# final.net
KiCad netlist of a schematic drawn in EAGLE
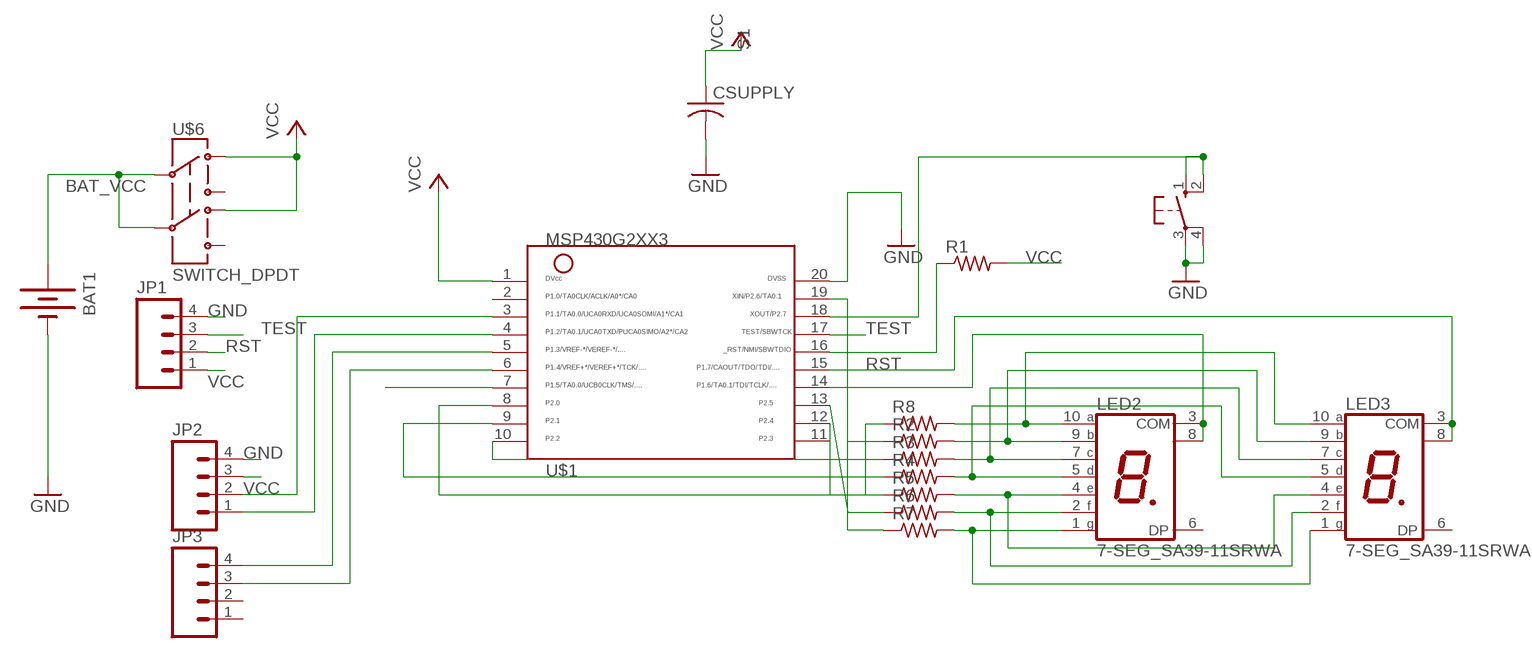
[diagram p0: schematic, sheet 1]

(export (version "E")
  (design (tool "Eeschema 10.0.6"))
  (components
    (comp (ref "BAT1")
      (value "BATTERYBU2032SM")
      (footprint "eagle-import:BU2032SM")
      (libsource (lib "eagle-import") (part "BATTERYBU2032SM"))
    )
    (comp (ref "CSUPPLY")
      (value "C-USC1206")
      (footprint "eagle-import:C1206")
      (libsource (lib "eagle-import") (part "C-USC1206"))
    )
    (comp (ref "JP1")
      (value "M04LOCK")
      (footprint "eagle-import:1X04_LOCK")
      (libsource (lib "eagle-import") (part "M04LOCK"))
    )
    (comp (ref "JP2")
      (value "M04LOCK")
      (footprint "eagle-import:1X04_LOCK")
      (libsource (lib "eagle-import") (part "M04LOCK"))
    )
    (comp (ref "JP3")
      (value "M04LOCK")
      (footprint "eagle-import:1X04_LOCK")
      (libsource (lib "eagle-import") (part "M04LOCK"))
    )
    (comp (ref "LED2")
      (value "7-SEG_SA39-11SRWA")
      (footprint "eagle-import:SA39-11SRWA")
      (libsource (lib "eagle-import") (part "7-SEG_SA39-11SRWA"))
    )
    (comp (ref "LED3")
      (value "7-SEG_SA39-11SRWA")
      (footprint "eagle-import:SA39-11SRWA")
      (libsource (lib "eagle-import") (part "7-SEG_SA39-11SRWA"))
    )
    (comp (ref "R1")
      (value "R-US_R1206")
      (footprint "eagle-import:R1206")
      (libsource (lib "eagle-import") (part "R-US_R1206"))
    )
    (comp (ref "R2")
      (value "R-US_R1206")
      (footprint "eagle-import:R1206")
      (libsource (lib "eagle-import") (part "R-US_R1206"))
    )
    (comp (ref "R3")
      (value "R-US_R1206")
      (footprint "eagle-import:R1206")
      (libsource (lib "eagle-import") (part "R-US_R1206"))
    )
    (comp (ref "R4")
      (value "R-US_R1206")
      (footprint "eagle-import:R1206")
      (libsource (lib "eagle-import") (part "R-US_R1206"))
    )
    (comp (ref "R5")
      (value "R-US_R1206")
      (footprint "eagle-import:R1206")
      (libsource (lib "eagle-import") (part "R-US_R1206"))
    )
    (comp (ref "R6")
      (value "R-US_R1206")
      (footprint "eagle-import:R1206")
      (libsource (lib "eagle-import") (part "R-US_R1206"))
    )
    (comp (ref "R7")
      (value "R-US_R1206")
      (footprint "eagle-import:R1206")
      (libsource (lib "eagle-import") (part "R-US_R1206"))
    )
    (comp (ref "R8")
      (value "R-US_R1206")
      (footprint "eagle-import:R1206")
      (libsource (lib "eagle-import") (part "R-US_R1206"))
    )
    (comp (ref "S1")
      (value "10-XX")
      (footprint "eagle-import:B3F-10XX")
      (fields (field (name "MPN") "B3F-1000"))
      (libsource (lib "eagle-import") (part "10-XX"))
    )
    (comp (ref "U$1")
      (value "MSP430G2XX3TSSOP")
      (footprint "eagle-import:PW20")
      (libsource (lib "eagle-import") (part "MSP430G2XX3TSSOP"))
    )
    (comp (ref "U$6")
      (value "SWITCH_DPDT")
      (footprint "eagle-import:JS_DPDT_TH")
      (libsource (lib "eagle-import") (part "SWITCH_DPDT"))
    )
  )
  (nets
    (net (code "1") (name "/BAT_VCC") (class "Default")
      (node (ref "BAT1") (pin "P$1") (pinfunction "+_P$1") (pintype "power_in"))
      (node (ref "U$6") (pin "2") (pinfunction "2_2") (pintype "bidirectional"))
      (node (ref "U$6") (pin "5") (pinfunction "5_5") (pintype "bidirectional"))
    )
    (net (code "2") (name "/RST") (class "Default")
      (node (ref "JP1") (pin "2") (pinfunction "2_2") (pintype "passive"))
      (node (ref "R1") (pin "1") (pinfunction "1_1") (pintype "passive"))
      (node (ref "U$1") (pin "16") (pinfunction "16_16") (pintype "bidirectional"))
    )
    (net (code "3") (name "/TEST") (class "Default")
      (node (ref "JP1") (pin "3") (pinfunction "3_3") (pintype "passive"))
      (node (ref "U$1") (pin "17") (pinfunction "17_17") (pintype "bidirectional"))
    )
    (net (code "4") (name "GND") (class "Default")
      (node (ref "BAT1") (pin "P$2") (pinfunction "-_P$2") (pintype "power_in"))
      (node (ref "CSUPPLY") (pin "2") (pinfunction "2_2") (pintype "passive"))
      (node (ref "JP1") (pin "4") (pinfunction "4_4") (pintype "passive"))
      (node (ref "JP2") (pin "4") (pinfunction "4_4") (pintype "passive"))
      (node (ref "S1") (pin "3") (pinfunction "P_3") (pintype "passive"))
      (node (ref "S1") (pin "4") (pinfunction "P1_4") (pintype "passive"))
      (node (ref "U$1") (pin "20") (pinfunction "20_20") (pintype "bidirectional"))
    )
    (net (code "5") (name "Net-(JP2-Pad1)") (class "Default")
      (node (ref "JP2") (pin "1") (pinfunction "1_1") (pintype "passive"))
      (node (ref "U$1") (pin "4") (pinfunction "4_4") (pintype "bidirectional"))
    )
    (net (code "6") (name "Net-(JP2-Pad2)") (class "Default")
      (node (ref "JP2") (pin "2") (pinfunction "2_2") (pintype "passive"))
      (node (ref "U$1") (pin "3") (pinfunction "3_3") (pintype "bidirectional"))
    )
    (net (code "7") (name "Net-(JP3-Pad3)") (class "Default")
      (node (ref "JP3") (pin "3") (pinfunction "3_3") (pintype "passive"))
      (node (ref "U$1") (pin "6") (pinfunction "6_6") (pintype "bidirectional"))
    )
    (net (code "8") (name "Net-(JP3-Pad4)") (class "Default")
      (node (ref "JP3") (pin "4") (pinfunction "4_4") (pintype "passive"))
      (node (ref "U$1") (pin "5") (pinfunction "5_5") (pintype "bidirectional"))
    )
    (net (code "9") (name "Net-(LED2-A)") (class "Default")
      (node (ref "LED2") (pin "10") (pinfunction "A_10") (pintype "passive"))
      (node (ref "LED3") (pin "10") (pinfunction "A_10") (pintype "passive"))
      (node (ref "R8") (pin "2") (pinfunction "2_2") (pintype "passive"))
    )
    (net (code "10") (name "Net-(LED2-B)") (class "Default")
      (node (ref "LED2") (pin "9") (pinfunction "B_9") (pintype "passive"))
      (node (ref "LED3") (pin "9") (pinfunction "B_9") (pintype "passive"))
      (node (ref "R2") (pin "2") (pinfunction "2_2") (pintype "passive"))
    )
    (net (code "11") (name "Net-(LED2-C)") (class "Default")
      (node (ref "LED2") (pin "7") (pinfunction "C_7") (pintype "passive"))
      (node (ref "LED3") (pin "7") (pinfunction "C_7") (pintype "passive"))
      (node (ref "R3") (pin "2") (pinfunction "2_2") (pintype "passive"))
    )
    (net (code "12") (name "Net-(LED2-COM-Pad3)") (class "Default")
      (node (ref "LED2") (pin "3") (pinfunction "COM_3") (pintype "passive"))
      (node (ref "LED2") (pin "8") (pinfunction "COM_8") (pintype "passive"))
      (node (ref "U$1") (pin "14") (pinfunction "14_14") (pintype "bidirectional"))
    )
    (net (code "13") (name "Net-(LED2-D)") (class "Default")
      (node (ref "LED2") (pin "5") (pinfunction "D_5") (pintype "passive"))
      (node (ref "LED3") (pin "5") (pinfunction "D_5") (pintype "passive"))
      (node (ref "R4") (pin "2") (pinfunction "2_2") (pintype "passive"))
    )
    (net (code "14") (name "Net-(LED2-E)") (class "Default")
      (node (ref "LED2") (pin "4") (pinfunction "E_4") (pintype "passive"))
      (node (ref "LED3") (pin "4") (pinfunction "E_4") (pintype "passive"))
      (node (ref "R5") (pin "2") (pinfunction "2_2") (pintype "passive"))
    )
    (net (code "15") (name "Net-(LED2-F)") (class "Default")
      (node (ref "LED2") (pin "2") (pinfunction "F_2") (pintype "passive"))
      (node (ref "LED3") (pin "2") (pinfunction "F_2") (pintype "passive"))
      (node (ref "R6") (pin "2") (pinfunction "2_2") (pintype "passive"))
    )
    (net (code "16") (name "Net-(LED2-G)") (class "Default")
      (node (ref "LED2") (pin "1") (pinfunction "G_1") (pintype "passive"))
      (node (ref "LED3") (pin "1") (pinfunction "G_1") (pintype "passive"))
      (node (ref "R7") (pin "2") (pinfunction "2_2") (pintype "passive"))
    )
    (net (code "17") (name "Net-(LED3-COM-Pad3)") (class "Default")
      (node (ref "LED3") (pin "3") (pinfunction "COM_3") (pintype "passive"))
      (node (ref "LED3") (pin "8") (pinfunction "COM_8") (pintype "passive"))
      (node (ref "U$1") (pin "15") (pinfunction "15_15") (pintype "bidirectional"))
    )
    (net (code "18") (name "Net-(R2-Pad1)") (class "Default")
      (node (ref "R2") (pin "1") (pinfunction "1_1") (pintype "passive"))
      (node (ref "U$1") (pin "9") (pinfunction "9_9") (pintype "bidirectional"))
    )
    (net (code "19") (name "Net-(R3-Pad1)") (class "Default")
      (node (ref "R3") (pin "1") (pinfunction "1_1") (pintype "passive"))
      (node (ref "U$1") (pin "10") (pinfunction "10_10") (pintype "bidirectional"))
    )
    (net (code "20") (name "Net-(R4-Pad1)") (class "Default")
      (node (ref "R4") (pin "1") (pinfunction "1_1") (pintype "passive"))
      (node (ref "U$1") (pin "11") (pinfunction "11_11") (pintype "bidirectional"))
    )
    (net (code "21") (name "Net-(R5-Pad1)") (class "Default")
      (node (ref "R5") (pin "1") (pinfunction "1_1") (pintype "passive"))
      (node (ref "U$1") (pin "12") (pinfunction "12_12") (pintype "bidirectional"))
    )
    (net (code "22") (name "Net-(R6-Pad1)") (class "Default")
      (node (ref "R6") (pin "1") (pinfunction "1_1") (pintype "passive"))
      (node (ref "U$1") (pin "13") (pinfunction "13_13") (pintype "bidirectional"))
    )
    (net (code "23") (name "Net-(R7-Pad1)") (class "Default")
      (node (ref "R7") (pin "1") (pinfunction "1_1") (pintype "passive"))
      (node (ref "U$1") (pin "19") (pinfunction "19_19") (pintype "bidirectional"))
    )
    (net (code "24") (name "Net-(R8-Pad1)") (class "Default")
      (node (ref "R8") (pin "1") (pinfunction "1_1") (pintype "passive"))
      (node (ref "U$1") (pin "8") (pinfunction "8_8") (pintype "bidirectional"))
    )
    (net (code "25") (name "Net-(S1-S)") (class "Default")
      (node (ref "S1") (pin "1") (pinfunction "S_1") (pintype "passive"))
      (node (ref "S1") (pin "2") (pinfunction "S1_2") (pintype "passive"))
      (node (ref "U$1") (pin "18") (pinfunction "18_18") (pintype "bidirectional"))
    )
    (net (code "26") (name "VCC") (class "Default")
      (node (ref "CSUPPLY") (pin "1") (pinfunction "1_1") (pintype "passive"))
      (node (ref "JP1") (pin "1") (pinfunction "1_1") (pintype "passive"))
      (node (ref "JP2") (pin "3") (pinfunction "3_3") (pintype "passive"))
      (node (ref "R1") (pin "2") (pinfunction "2_2") (pintype "passive"))
      (node (ref "U$1") (pin "1") (pinfunction "1_1") (pintype "bidirectional"))
      (node (ref "U$6") (pin "1") (pinfunction "1_1") (pintype "bidirectional"))
      (node (ref "U$6") (pin "4") (pinfunction "4_4") (pintype "bidirectional"))
    )
    (net (code "27") (name "unconnected-(JP3-Pad1)") (class "Default")
      (node (ref "JP3") (pin "1") (pinfunction "1_1") (pintype "passive"))
    )
    (net (code "28") (name "unconnected-(JP3-Pad2)") (class "Default")
      (node (ref "JP3") (pin "2") (pinfunction "2_2") (pintype "passive"))
    )
    (net (code "29") (name "unconnected-(LED2-DP-Pad6)") (class "Default")
      (node (ref "LED2") (pin "6") (pinfunction "DP_6") (pintype "passive"))
    )
    (net (code "30") (name "unconnected-(LED3-DP-Pad6)") (class "Default")
      (node (ref "LED3") (pin "6") (pinfunction "DP_6") (pintype "passive"))
    )
    (net (code "31") (name "unconnected-(U$1-Pad2)") (class "Default")
      (node (ref "U$1") (pin "2") (pinfunction "2_2") (pintype "bidirectional"))
    )
    (net (code "32") (name "unconnected-(U$1-Pad7)") (class "Default")
      (node (ref "U$1") (pin "7") (pinfunction "7_7") (pintype "bidirectional"))
    )
    (net (code "33") (name "unconnected-(U$6-Pad3)") (class "Default")
      (node (ref "U$6") (pin "3") (pinfunction "3_3") (pintype "bidirectional"))
    )
    (net (code "34") (name "unconnected-(U$6-Pad6)") (class "Default")
      (node (ref "U$6") (pin "6") (pinfunction "6_6") (pintype "bidirectional"))
    )
  )
)
